# LEDs.net
KiCad netlist of a schematic drawn in Altium Designer
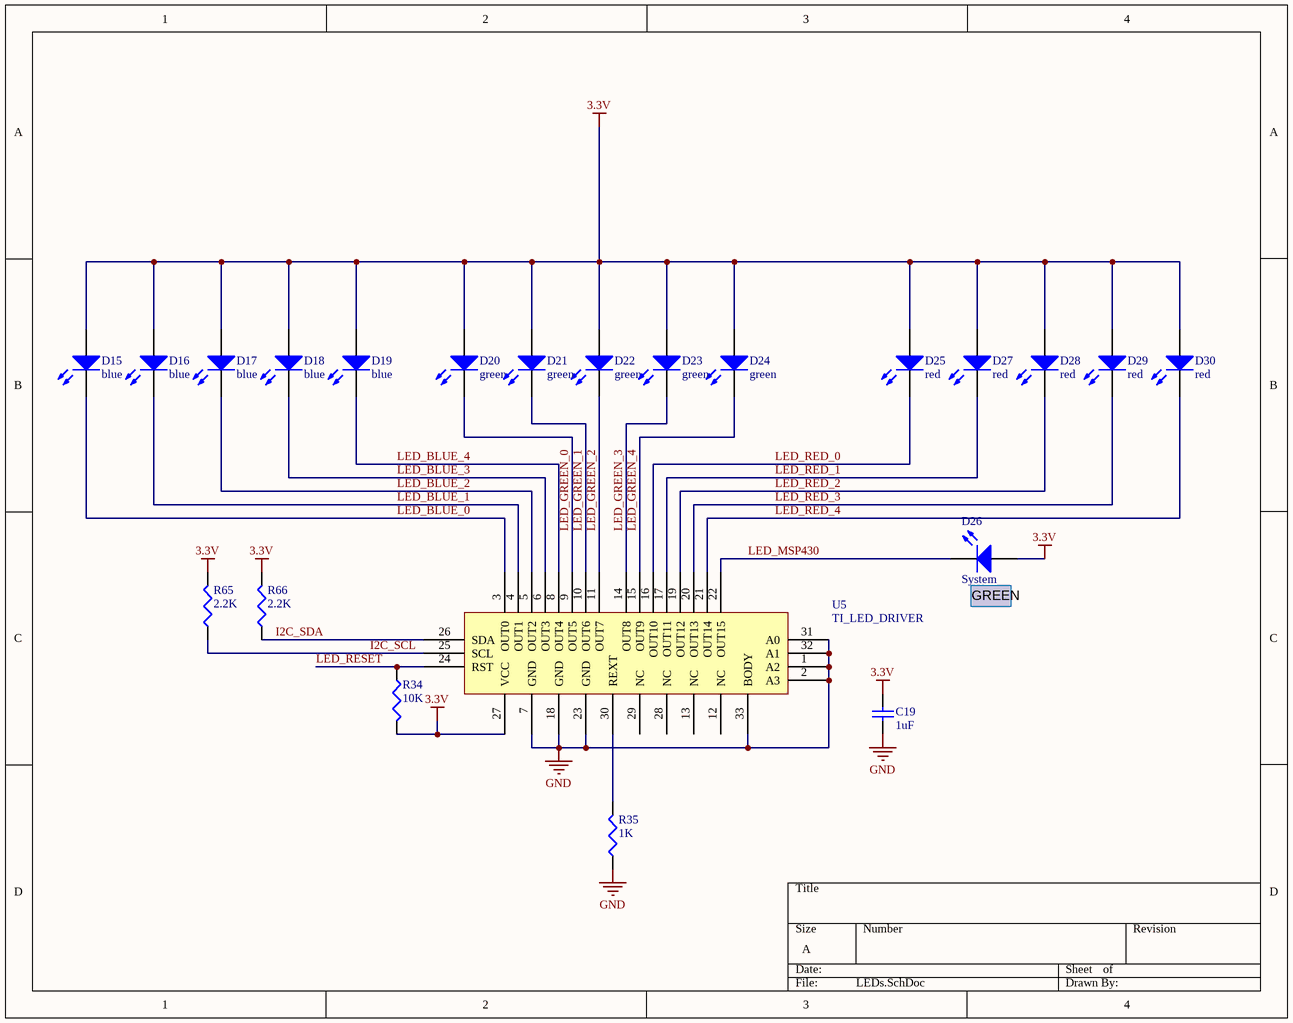
[diagram p0: LEDs.SchDoc]

(export (version "E")
  (design (tool "Eeschema 10.0.6"))
  (components
    (comp (ref "C19")
      (value "1uF")
      (footprint "CAPC1608L")
      (description "Capacitor (Semiconductor SIM Model)")
      (fields
        (field (name "PART NUMBER") "C1608Y5V1C105Z")
        (field (name "MANUFACTURER") "TDK")
        (field (name "PUBLISHER") "Altium Limited")
      )
      (libsource (lib "Miscellaneous Devices") (part "Cap Semi"))
    )
    (comp (ref "D15")
      (value "blue")
      (footprint "SurfaceMount(603)")
      (fields (field (name "PART NUMBER") "LB Q39G-L2N2-35-1") (field (name "MANUFACTURER") "Osram"))
      (libsource (lib "") (part "LED_1"))
    )
    (comp (ref "D16")
      (value "blue")
      (footprint "SurfaceMount(603)")
      (fields (field (name "PART NUMBER") "LB Q39G-L2N2-35-1") (field (name "MANUFACTURER") "Osram"))
      (libsource (lib "") (part "LED_1"))
    )
    (comp (ref "D17")
      (value "blue")
      (footprint "SurfaceMount(603)")
      (fields (field (name "PART NUMBER") "LB Q39G-L2N2-35-1") (field (name "MANUFACTURER") "Osram"))
      (libsource (lib "") (part "LED_1"))
    )
    (comp (ref "D18")
      (value "blue")
      (footprint "SurfaceMount(603)")
      (fields (field (name "PART NUMBER") "LB Q39G-L2N2-35-1") (field (name "MANUFACTURER") "Osram"))
      (libsource (lib "") (part "LED_1"))
    )
    (comp (ref "D19")
      (value "blue")
      (footprint "SurfaceMount(603)")
      (fields (field (name "PART NUMBER") "LB Q39G-L2N2-35-1") (field (name "MANUFACTURER") "Osram"))
      (libsource (lib "") (part "LED_1"))
    )
    (comp (ref "D20")
      (value "green")
      (footprint "SurfaceMount(603)")
      (fields (field (name "PART NUMBER") "LNJ612W8WRA") (field (name "MANUFACTURER") "Panasonic"))
      (libsource (lib "") (part "LED_1"))
    )
    (comp (ref "D21")
      (value "green")
      (footprint "SurfaceMount(603)")
      (fields (field (name "PART NUMBER") "LNJ612W8WRA") (field (name "MANUFACTURER") "Panasonic"))
      (libsource (lib "") (part "LED_1"))
    )
    (comp (ref "D22")
      (value "green")
      (footprint "SurfaceMount(603)")
      (fields (field (name "PART NUMBER") "LNJ612W8WRA") (field (name "MANUFACTURER") "Panasonic"))
      (libsource (lib "") (part "LED_1"))
    )
    (comp (ref "D23")
      (value "green")
      (footprint "SurfaceMount(603)")
      (fields (field (name "PART NUMBER") "LNJ612W8WRA") (field (name "MANUFACTURER") "Panasonic"))
      (libsource (lib "") (part "LED_1"))
    )
    (comp (ref "D24")
      (value "green")
      (footprint "SurfaceMount(603)")
      (fields (field (name "PART NUMBER") "LNJ612W8WRA") (field (name "MANUFACTURER") "Panasonic"))
      (libsource (lib "") (part "LED_1"))
    )
    (comp (ref "D25")
      (value "red")
      (footprint "SurfaceMount(603)")
      (fields (field (name "PART NUMBER") "LS Q976-NR-1") (field (name "MANUFACTURER") "Osram"))
      (libsource (lib "") (part "LED_1"))
    )
    (comp (ref "D26")
      (value "System")
      (footprint "SurfaceMount(603)")
      (fields (field (name "PART NUMBER") "LNJ612W8WRA") (field (name "MANUFACTURER") "Panasonic"))
      (libsource (lib "mrone") (part "LED"))
    )
    (comp (ref "D27")
      (value "red")
      (footprint "SurfaceMount(603)")
      (fields (field (name "PART NUMBER") "LS Q976-NR-1") (field (name "MANUFACTURER") "Osram"))
      (libsource (lib "") (part "LED_1"))
    )
    (comp (ref "D28")
      (value "red")
      (footprint "SurfaceMount(603)")
      (fields (field (name "PART NUMBER") "LS Q976-NR-1") (field (name "MANUFACTURER") "Osram"))
      (libsource (lib "") (part "LED_1"))
    )
    (comp (ref "D29")
      (value "red")
      (footprint "SurfaceMount(603)")
      (fields (field (name "PART NUMBER") "LS Q976-NR-1") (field (name "MANUFACTURER") "Osram"))
      (libsource (lib "") (part "LED_1"))
    )
    (comp (ref "D30")
      (value "red")
      (footprint "SurfaceMount(603)")
      (fields (field (name "PART NUMBER") "LS Q976-NR-1") (field (name "MANUFACTURER") "Osram"))
      (libsource (lib "") (part "LED_1"))
    )
    (comp (ref "R34")
      (value "10K")
      (footprint "RESC1608L")
      (description "Resistor")
      (fields
        (field (name "PART NUMBER") "SR03-1002")
        (field (name "MANUFACTURER") "Vishay")
        (field (name "PUBLISHER") "Altium Limited")
      )
      (libsource (lib "Miscellaneous Devices") (part "Res3"))
    )
    (comp (ref "R35")
      (value "1K")
      (footprint "RESC1608L")
      (description "Resistor")
      (fields
        (field (name "PART NUMBER") "SR03-1001")
        (field (name "MANUFACTURER") "Vishay")
        (field (name "PUBLISHER") "Altium Limited")
      )
      (libsource (lib "Miscellaneous Devices") (part "Res3"))
    )
    (comp (ref "R65")
      (value "2.2K")
      (footprint "RESC1608L")
      (description "Resistor")
      (fields
        (field (name "PART NUMBER") "ERJ-3GEYJ-222V")
        (field (name "MANUFACTURER") "Panasonic")
        (field (name "PUBLISHER") "Altium Limited")
      )
      (libsource (lib "Miscellaneous Devices") (part "Res3"))
    )
    (comp (ref "R66")
      (value "2.2K")
      (footprint "RESC1608L")
      (description "Resistor")
      (fields
        (field (name "PART NUMBER") "ERJ-3GEYJ-222V")
        (field (name "MANUFACTURER") "Panasonic")
        (field (name "PUBLISHER") "Altium Limited")
      )
      (libsource (lib "Miscellaneous Devices") (part "Res3"))
    )
    (comp (ref "U5")
      (value "TI_LED_DRIVER")
      (footprint "QFN32-LEDTLC59116")
      (fields (field (name "PART NUMBER") "TLC59116IRHBR") (field (name "MANUFACTURER") "TI"))
      (libsource (lib "mrone") (part "TLC59116LEDDRIVER"))
    )
  )
  (nets
    (net (code "1") (name "/I2C_SCL") (class "Default")
      (node (ref "R65") (pin "1") (pinfunction "1_1") (pintype "passive"))
      (node (ref "U5") (pin "25") (pinfunction "SCL_25") (pintype "passive"))
    )
    (net (code "2") (name "/I2C_SDA") (class "Default")
      (node (ref "R66") (pin "1") (pinfunction "1_1") (pintype "passive"))
      (node (ref "U5") (pin "26") (pinfunction "SDA_26") (pintype "passive"))
    )
    (net (code "3") (name "/LED_BLUE_0") (class "Default")
      (node (ref "D15") (pin "2") (pinfunction "K_2") (pintype "passive"))
      (node (ref "U5") (pin "3") (pinfunction "OUT0_3") (pintype "passive"))
    )
    (net (code "4") (name "/LED_BLUE_1") (class "Default")
      (node (ref "D16") (pin "2") (pinfunction "K_2") (pintype "passive"))
      (node (ref "U5") (pin "4") (pinfunction "OUT1_4") (pintype "passive"))
    )
    (net (code "5") (name "/LED_BLUE_2") (class "Default")
      (node (ref "D17") (pin "2") (pinfunction "K_2") (pintype "passive"))
      (node (ref "U5") (pin "5") (pinfunction "OUT2_5") (pintype "passive"))
    )
    (net (code "6") (name "/LED_BLUE_3") (class "Default")
      (node (ref "D18") (pin "2") (pinfunction "K_2") (pintype "passive"))
      (node (ref "U5") (pin "6") (pinfunction "OUT3_6") (pintype "passive"))
    )
    (net (code "7") (name "/LED_BLUE_4") (class "Default")
      (node (ref "D19") (pin "2") (pinfunction "K_2") (pintype "passive"))
      (node (ref "U5") (pin "8") (pinfunction "OUT4_8") (pintype "passive"))
    )
    (net (code "8") (name "/LED_GREEN_0") (class "Default")
      (node (ref "D20") (pin "2") (pinfunction "K_2") (pintype "passive"))
      (node (ref "U5") (pin "9") (pinfunction "OUT5_9") (pintype "passive"))
    )
    (net (code "9") (name "/LED_GREEN_1") (class "Default")
      (node (ref "D21") (pin "2") (pinfunction "K_2") (pintype "passive"))
      (node (ref "U5") (pin "10") (pinfunction "OUT6_10") (pintype "passive"))
    )
    (net (code "10") (name "/LED_GREEN_2") (class "Default")
      (node (ref "D22") (pin "2") (pinfunction "K_2") (pintype "passive"))
      (node (ref "U5") (pin "11") (pinfunction "OUT7_11") (pintype "passive"))
    )
    (net (code "11") (name "/LED_GREEN_3") (class "Default")
      (node (ref "D23") (pin "2") (pinfunction "K_2") (pintype "passive"))
      (node (ref "U5") (pin "14") (pinfunction "OUT8_14") (pintype "passive"))
    )
    (net (code "12") (name "/LED_GREEN_4") (class "Default")
      (node (ref "D24") (pin "2") (pinfunction "K_2") (pintype "passive"))
      (node (ref "U5") (pin "15") (pinfunction "OUT9_15") (pintype "passive"))
    )
    (net (code "13") (name "/LED_MSP430") (class "Default")
      (node (ref "D26") (pin "2") (pinfunction "K_2") (pintype "passive"))
      (node (ref "U5") (pin "22") (pinfunction "OUT15_22") (pintype "passive"))
    )
    (net (code "14") (name "/LED_RED_0") (class "Default")
      (node (ref "D25") (pin "2") (pinfunction "K_2") (pintype "passive"))
      (node (ref "U5") (pin "16") (pinfunction "OUT10_16") (pintype "passive"))
    )
    (net (code "15") (name "/LED_RED_1") (class "Default")
      (node (ref "D27") (pin "2") (pinfunction "K_2") (pintype "passive"))
      (node (ref "U5") (pin "17") (pinfunction "OUT11_17") (pintype "passive"))
    )
    (net (code "16") (name "/LED_RED_2") (class "Default")
      (node (ref "D28") (pin "2") (pinfunction "K_2") (pintype "passive"))
      (node (ref "U5") (pin "19") (pinfunction "OUT12_19") (pintype "passive"))
    )
    (net (code "17") (name "/LED_RED_3") (class "Default")
      (node (ref "D29") (pin "2") (pinfunction "K_2") (pintype "passive"))
      (node (ref "U5") (pin "20") (pinfunction "OUT13_20") (pintype "passive"))
    )
    (net (code "18") (name "/LED_RED_4") (class "Default")
      (node (ref "D30") (pin "2") (pinfunction "K_2") (pintype "passive"))
      (node (ref "U5") (pin "21") (pinfunction "OUT14_21") (pintype "passive"))
    )
    (net (code "19") (name "/LED_RESET") (class "Default")
      (node (ref "R34") (pin "1") (pinfunction "1_1") (pintype "passive"))
      (node (ref "U5") (pin "24") (pinfunction "RST_24") (pintype "passive"))
    )
    (net (code "20") (name "3.3V") (class "Default")
      (node (ref "C19") (pin "2") (pinfunction "2_2") (pintype "passive"))
      (node (ref "D15") (pin "1") (pinfunction "A_1") (pintype "passive"))
      (node (ref "D16") (pin "1") (pinfunction "A_1") (pintype "passive"))
      (node (ref "D17") (pin "1") (pinfunction "A_1") (pintype "passive"))
      (node (ref "D18") (pin "1") (pinfunction "A_1") (pintype "passive"))
      (node (ref "D19") (pin "1") (pinfunction "A_1") (pintype "passive"))
      (node (ref "D20") (pin "1") (pinfunction "A_1") (pintype "passive"))
      (node (ref "D21") (pin "1") (pinfunction "A_1") (pintype "passive"))
      (node (ref "D22") (pin "1") (pinfunction "A_1") (pintype "passive"))
      (node (ref "D23") (pin "1") (pinfunction "A_1") (pintype "passive"))
      (node (ref "D24") (pin "1") (pinfunction "A_1") (pintype "passive"))
      (node (ref "D25") (pin "1") (pinfunction "A_1") (pintype "passive"))
      (node (ref "D26") (pin "1") (pinfunction "A_1") (pintype "passive"))
      (node (ref "D27") (pin "1") (pinfunction "A_1") (pintype "passive"))
      (node (ref "D28") (pin "1") (pinfunction "A_1") (pintype "passive"))
      (node (ref "D29") (pin "1") (pinfunction "A_1") (pintype "passive"))
      (node (ref "D30") (pin "1") (pinfunction "A_1") (pintype "passive"))
      (node (ref "R34") (pin "2") (pinfunction "2_2") (pintype "passive"))
      (node (ref "R65") (pin "2") (pinfunction "2_2") (pintype "passive"))
      (node (ref "R66") (pin "2") (pinfunction "2_2") (pintype "passive"))
      (node (ref "U5") (pin "27") (pinfunction "VCC_27") (pintype "passive"))
    )
    (net (code "21") (name "GND") (class "Default")
      (node (ref "C19") (pin "1") (pinfunction "1_1") (pintype "passive"))
      (node (ref "R35") (pin "1") (pinfunction "1_1") (pintype "passive"))
      (node (ref "U5") (pin "1") (pinfunction "A2_1") (pintype "passive"))
      (node (ref "U5") (pin "18") (pinfunction "GND_18") (pintype "passive"))
      (node (ref "U5") (pin "2") (pinfunction "A3_2") (pintype "passive"))
      (node (ref "U5") (pin "23") (pinfunction "GND_23") (pintype "passive"))
      (node (ref "U5") (pin "31") (pinfunction "A0_31") (pintype "passive"))
      (node (ref "U5") (pin "32") (pinfunction "A1_32") (pintype "passive"))
      (node (ref "U5") (pin "33") (pinfunction "BODY_33") (pintype "passive"))
      (node (ref "U5") (pin "7") (pinfunction "GND_7") (pintype "passive"))
    )
    (net (code "22") (name "Net-(U5-REXT)") (class "Default")
      (node (ref "R35") (pin "2") (pinfunction "2_2") (pintype "passive"))
      (node (ref "U5") (pin "30") (pinfunction "REXT_30") (pintype "passive"))
    )
    (net (code "23") (name "unconnected-(U5-NC-Pad12)") (class "Default")
      (node (ref "U5") (pin "12") (pinfunction "NC_12") (pintype "passive"))
    )
    (net (code "24") (name "unconnected-(U5-NC-Pad13)") (class "Default")
      (node (ref "U5") (pin "13") (pinfunction "NC_13") (pintype "passive"))
    )
    (net (code "25") (name "unconnected-(U5-NC-Pad28)") (class "Default")
      (node (ref "U5") (pin "28") (pinfunction "NC_28") (pintype "passive"))
    )
    (net (code "26") (name "unconnected-(U5-NC-Pad29)") (class "Default")
      (node (ref "U5") (pin "29") (pinfunction "NC_29") (pintype "passive"))
    )
  )
)
